# Mechanical_Interfacing.net
KiCad netlist of a schematic drawn in Altium Designer
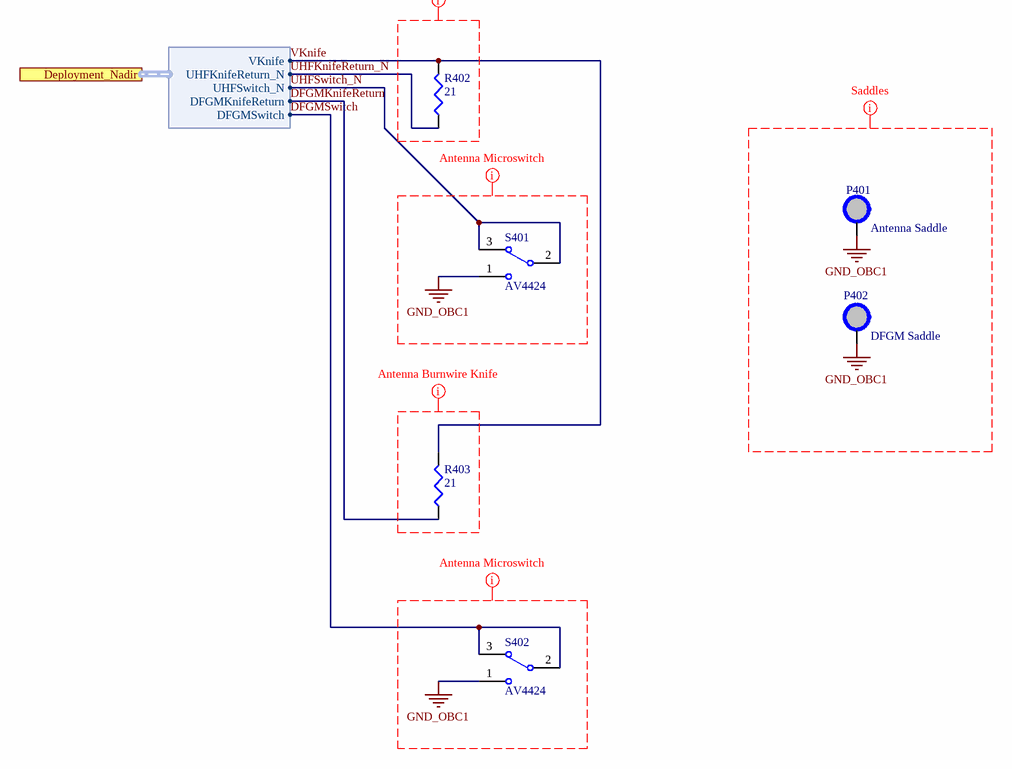
[diagram p0: Mechanical Interfacing.SchDoc]

(export (version "E")
  (design (tool "Eeschema 10.0.6"))
  (components
    (comp (ref "P401")
      (value "Antenna Saddle")
      (footprint "ANTENNA_SADDLE")
      (fields
        (field (name "PART NUMBER") "PXX-ABS-00001")
        (field (name "MANUFACTURER PART NUMBER") "Custom")
        (field (name "PUBLISHER") "AlbertaSat")
      )
      (libsource (lib "Database") (part "Mounting_Hole"))
    )
    (comp (ref "P402")
      (value "DFGM Saddle")
      (footprint "DFGM_Saddle")
      (fields
        (field (name "PART NUMBER") "PXX-ABS-00010")
        (field (name "MANUFACTURER PART NUMBER") "Custom")
        (field (name "PUBLISHER") "AlbertaSat")
      )
      (libsource (lib "Database") (part "Mounting_Hole"))
    )
    (comp (ref "R402")
      (value "21")
      (footprint "VSH-CPF1")
      (description "21 Ohms ±1% 1W Through Hole Resistor Axial Flame Proof, Moisture Resistant, Safety Metal Film")
      (fields
        (field (name "PART NUMBER") "PR-VSH-00317")
        (field (name "MANUFACTURER PART NUMBER") "CPF121R000FKEE6")
        (field (name "PUBLISHER") "AlbertaSat")
      )
      (libsource (lib "Database") (part "Res3"))
    )
    (comp (ref "R403")
      (value "21")
      (footprint "VSH-CPF1")
      (description "21 Ohms ±1% 1W Through Hole Resistor Axial Flame Proof, Moisture Resistant, Safety Metal Film")
      (fields
        (field (name "PART NUMBER") "PR-VSH-00317")
        (field (name "MANUFACTURER PART NUMBER") "CPF121R000FKEE6")
        (field (name "PUBLISHER") "AlbertaSat")
      )
      (libsource (lib "Database") (part "Res3"))
    )
    (comp (ref "S401")
      (value "AV4424")
      (footprint "PANA-AV4424")
      (description "SWITCH SNAP ACT SPDT 500MA 30V")
      (fields (field (name "PART NUMBER") "20035"))
      (libsource (lib "Database") (part "SW-SPDT"))
    )
    (comp (ref "S402")
      (value "AV4424")
      (footprint "PANA-AV4424")
      (description "SWITCH SNAP ACT SPDT 500MA 30V")
      (fields (field (name "PART NUMBER") "20035"))
      (libsource (lib "Database") (part "SW-SPDT"))
    )
  )
  (nets
    (net (code "2") (name "/DFGMKnifeReturn") (class "Default")
      (node (ref "R403") (pin "1") (pinfunction "1_1") (pintype "passive"))
    )
    (net (code "3") (name "/DFGMSwitch") (class "Default")
      (node (ref "S402") (pin "2") (pinfunction "COM_2") (pintype "passive"))
      (node (ref "S402") (pin "3") (pinfunction "NC_3") (pintype "passive"))
    )
    (net (code "4") (name "/UHFKnifeReturn_N") (class "Default")
      (node (ref "R402") (pin "1") (pinfunction "1_1") (pintype "passive"))
    )
    (net (code "5") (name "/UHFSwitch_N") (class "Default")
      (node (ref "S401") (pin "2") (pinfunction "COM_2") (pintype "passive"))
      (node (ref "S401") (pin "3") (pinfunction "NC_3") (pintype "passive"))
    )
    (net (code "6") (name "/VKnife") (class "Default")
      (node (ref "R402") (pin "2") (pinfunction "2_2") (pintype "passive"))
      (node (ref "R403") (pin "2") (pinfunction "2_2") (pintype "passive"))
    )
    (net (code "8") (name "GND_OBC1") (class "Default")
      (node (ref "P401") (pin "1") (pinfunction "0_1") (pintype "passive"))
      (node (ref "P402") (pin "1") (pinfunction "0_1") (pintype "passive"))
      (node (ref "S401") (pin "1") (pinfunction "NO_1") (pintype "passive"))
      (node (ref "S402") (pin "1") (pinfunction "NO_1") (pintype "passive"))
    )
  )
)
